# controller-batpack.net
KiCad netlist of a schematic drawn in EAGLE
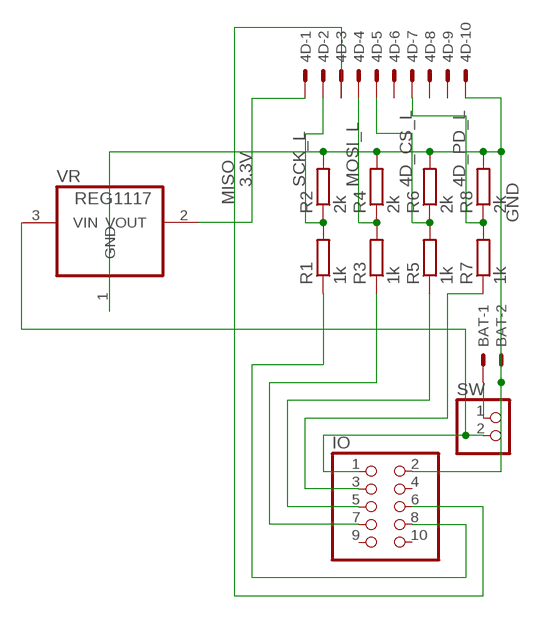
[diagram p0: schematic, sheet 1]

(export (version "E")
  (design (tool "Eeschema 10.0.6"))
  (components
    (comp (ref "4D")
      (value "52745-1090")
      (footprint "eagle-import:52745-1090")
      (libsource (lib "eagle-import") (part "52745-1090"))
    )
    (comp (ref "BAT")
      (value "22-23-2021")
      (footprint "eagle-import:22-23-2021")
      (fields (field (name "MF") "MOLEX"))
      (libsource (lib "eagle-import") (part "22-23-2021"))
    )
    (comp (ref "IO")
      (value "PINHD-2X5/90")
      (footprint "eagle-import:2X05_90")
      (libsource (lib "eagle-import") (part "PINHD-2X5/90"))
    )
    (comp (ref "R1")
      (value "1k")
      (footprint "eagle-import:M1206")
      (libsource (lib "eagle-import") (part "R-EU_M1206"))
    )
    (comp (ref "R2")
      (value "2k")
      (footprint "eagle-import:M1206")
      (libsource (lib "eagle-import") (part "R-EU_M1206"))
    )
    (comp (ref "R3")
      (value "1k")
      (footprint "eagle-import:M1206")
      (libsource (lib "eagle-import") (part "R-EU_M1206"))
    )
    (comp (ref "R4")
      (value "2k")
      (footprint "eagle-import:M1206")
      (libsource (lib "eagle-import") (part "R-EU_M1206"))
    )
    (comp (ref "R5")
      (value "1k")
      (footprint "eagle-import:M1206")
      (libsource (lib "eagle-import") (part "R-EU_M1206"))
    )
    (comp (ref "R6")
      (value "2k")
      (footprint "eagle-import:M1206")
      (libsource (lib "eagle-import") (part "R-EU_M1206"))
    )
    (comp (ref "R7")
      (value "1k")
      (footprint "eagle-import:M1206")
      (libsource (lib "eagle-import") (part "R-EU_M1206"))
    )
    (comp (ref "R8")
      (value "2k")
      (footprint "eagle-import:M1206")
      (libsource (lib "eagle-import") (part "R-EU_M1206"))
    )
    (comp (ref "SW")
      (value "PINHD-1X2/90")
      (footprint "eagle-import:1X02_90")
      (libsource (lib "eagle-import") (part "PINHD-1X2/90"))
    )
    (comp (ref "VR")
      (value "REG1117")
      (footprint "eagle-import:SOT223")
      (libsource (lib "eagle-import") (part "REG1117"))
    )
  )
  (nets
    (net (code "1") (name "/3.3V") (class "Default")
      (node (ref "4D") (pin "1") (pinfunction "S_1") (pintype "passive"))
      (node (ref "VR") (pin "2") (pinfunction "VOUT_2") (pintype "output"))
    )
    (net (code "2") (name "/4D_CS_L") (class "Default")
      (node (ref "4D") (pin "5") (pinfunction "S_5") (pintype "passive"))
      (node (ref "R5") (pin "2") (pinfunction "2_2") (pintype "passive"))
      (node (ref "R6") (pin "1") (pinfunction "1_1") (pintype "passive"))
    )
    (net (code "3") (name "/4D_PD_L") (class "Default")
      (node (ref "4D") (pin "7") (pinfunction "S_7") (pintype "passive"))
      (node (ref "R7") (pin "2") (pinfunction "2_2") (pintype "passive"))
      (node (ref "R8") (pin "1") (pinfunction "1_1") (pintype "passive"))
    )
    (net (code "4") (name "/GND") (class "Default")
      (node (ref "4D") (pin "10") (pinfunction "S_10") (pintype "passive"))
      (node (ref "BAT") (pin "2") (pinfunction "S_2") (pintype "passive"))
      (node (ref "IO") (pin "2") (pinfunction "2_2") (pintype "passive"))
      (node (ref "R2") (pin "2") (pinfunction "2_2") (pintype "passive"))
      (node (ref "R4") (pin "2") (pinfunction "2_2") (pintype "passive"))
      (node (ref "R6") (pin "2") (pinfunction "2_2") (pintype "passive"))
      (node (ref "R8") (pin "2") (pinfunction "2_2") (pintype "passive"))
      (node (ref "VR") (pin "1") (pinfunction "GND_1") (pintype "power_in"))
    )
    (net (code "5") (name "/MISO") (class "Default")
      (node (ref "4D") (pin "3") (pinfunction "S_3") (pintype "passive"))
      (node (ref "IO") (pin "6") (pinfunction "6_6") (pintype "passive"))
    )
    (net (code "6") (name "/MOSI_L") (class "Default")
      (node (ref "4D") (pin "4") (pinfunction "S_4") (pintype "passive"))
      (node (ref "R3") (pin "2") (pinfunction "2_2") (pintype "passive"))
      (node (ref "R4") (pin "1") (pinfunction "1_1") (pintype "passive"))
    )
    (net (code "7") (name "/SCK_L") (class "Default")
      (node (ref "4D") (pin "2") (pinfunction "S_2") (pintype "passive"))
      (node (ref "R1") (pin "2") (pinfunction "2_2") (pintype "passive"))
      (node (ref "R2") (pin "1") (pinfunction "1_1") (pintype "passive"))
    )
    (net (code "8") (name "Net-(BATA-S)") (class "Default")
      (node (ref "BAT") (pin "1") (pinfunction "S_1") (pintype "passive"))
      (node (ref "SW") (pin "1") (pinfunction "1_1") (pintype "passive"))
    )
    (net (code "9") (name "Net-(IO-Pad3)") (class "Default")
      (node (ref "IO") (pin "3") (pinfunction "3_3") (pintype "passive"))
      (node (ref "R7") (pin "1") (pinfunction "1_1") (pintype "passive"))
    )
    (net (code "10") (name "Net-(IO-Pad5)") (class "Default")
      (node (ref "IO") (pin "5") (pinfunction "5_5") (pintype "passive"))
      (node (ref "R5") (pin "1") (pinfunction "1_1") (pintype "passive"))
    )
    (net (code "11") (name "Net-(IO-Pad7)") (class "Default")
      (node (ref "IO") (pin "7") (pinfunction "7_7") (pintype "passive"))
      (node (ref "R3") (pin "1") (pinfunction "1_1") (pintype "passive"))
    )
    (net (code "12") (name "Net-(IO-Pad8)") (class "Default")
      (node (ref "IO") (pin "8") (pinfunction "8_8") (pintype "passive"))
      (node (ref "R1") (pin "1") (pinfunction "1_1") (pintype "passive"))
    )
    (net (code "13") (name "Net-(VR-VIN)") (class "Default")
      (node (ref "IO") (pin "1") (pinfunction "1_1") (pintype "passive"))
      (node (ref "SW") (pin "2") (pinfunction "2_2") (pintype "passive"))
      (node (ref "VR") (pin "3") (pinfunction "VIN_3") (pintype "input"))
    )
    (net (code "14") (name "unconnected-(4DG-S-Pad6)") (class "Default")
      (node (ref "4D") (pin "6") (pinfunction "S_6") (pintype "passive"))
    )
    (net (code "15") (name "unconnected-(4DI-S-Pad8)") (class "Default")
      (node (ref "4D") (pin "8") (pinfunction "S_8") (pintype "passive"))
    )
    (net (code "16") (name "unconnected-(4DJ-S-Pad9)") (class "Default")
      (node (ref "4D") (pin "9") (pinfunction "S_9") (pintype "passive"))
    )
    (net (code "17") (name "unconnected-(IO-Pad4)") (class "Default")
      (node (ref "IO") (pin "4") (pinfunction "4_4") (pintype "passive"))
    )
    (net (code "18") (name "unconnected-(IO-Pad9)") (class "Default")
      (node (ref "IO") (pin "9") (pinfunction "9_9") (pintype "passive"))
    )
    (net (code "19") (name "unconnected-(IO-Pad10)") (class "Default")
      (node (ref "IO") (pin "10") (pinfunction "10_10") (pintype "passive"))
    )
  )
)
